# M002X.net
KiCad netlist of a schematic drawn in EAGLE
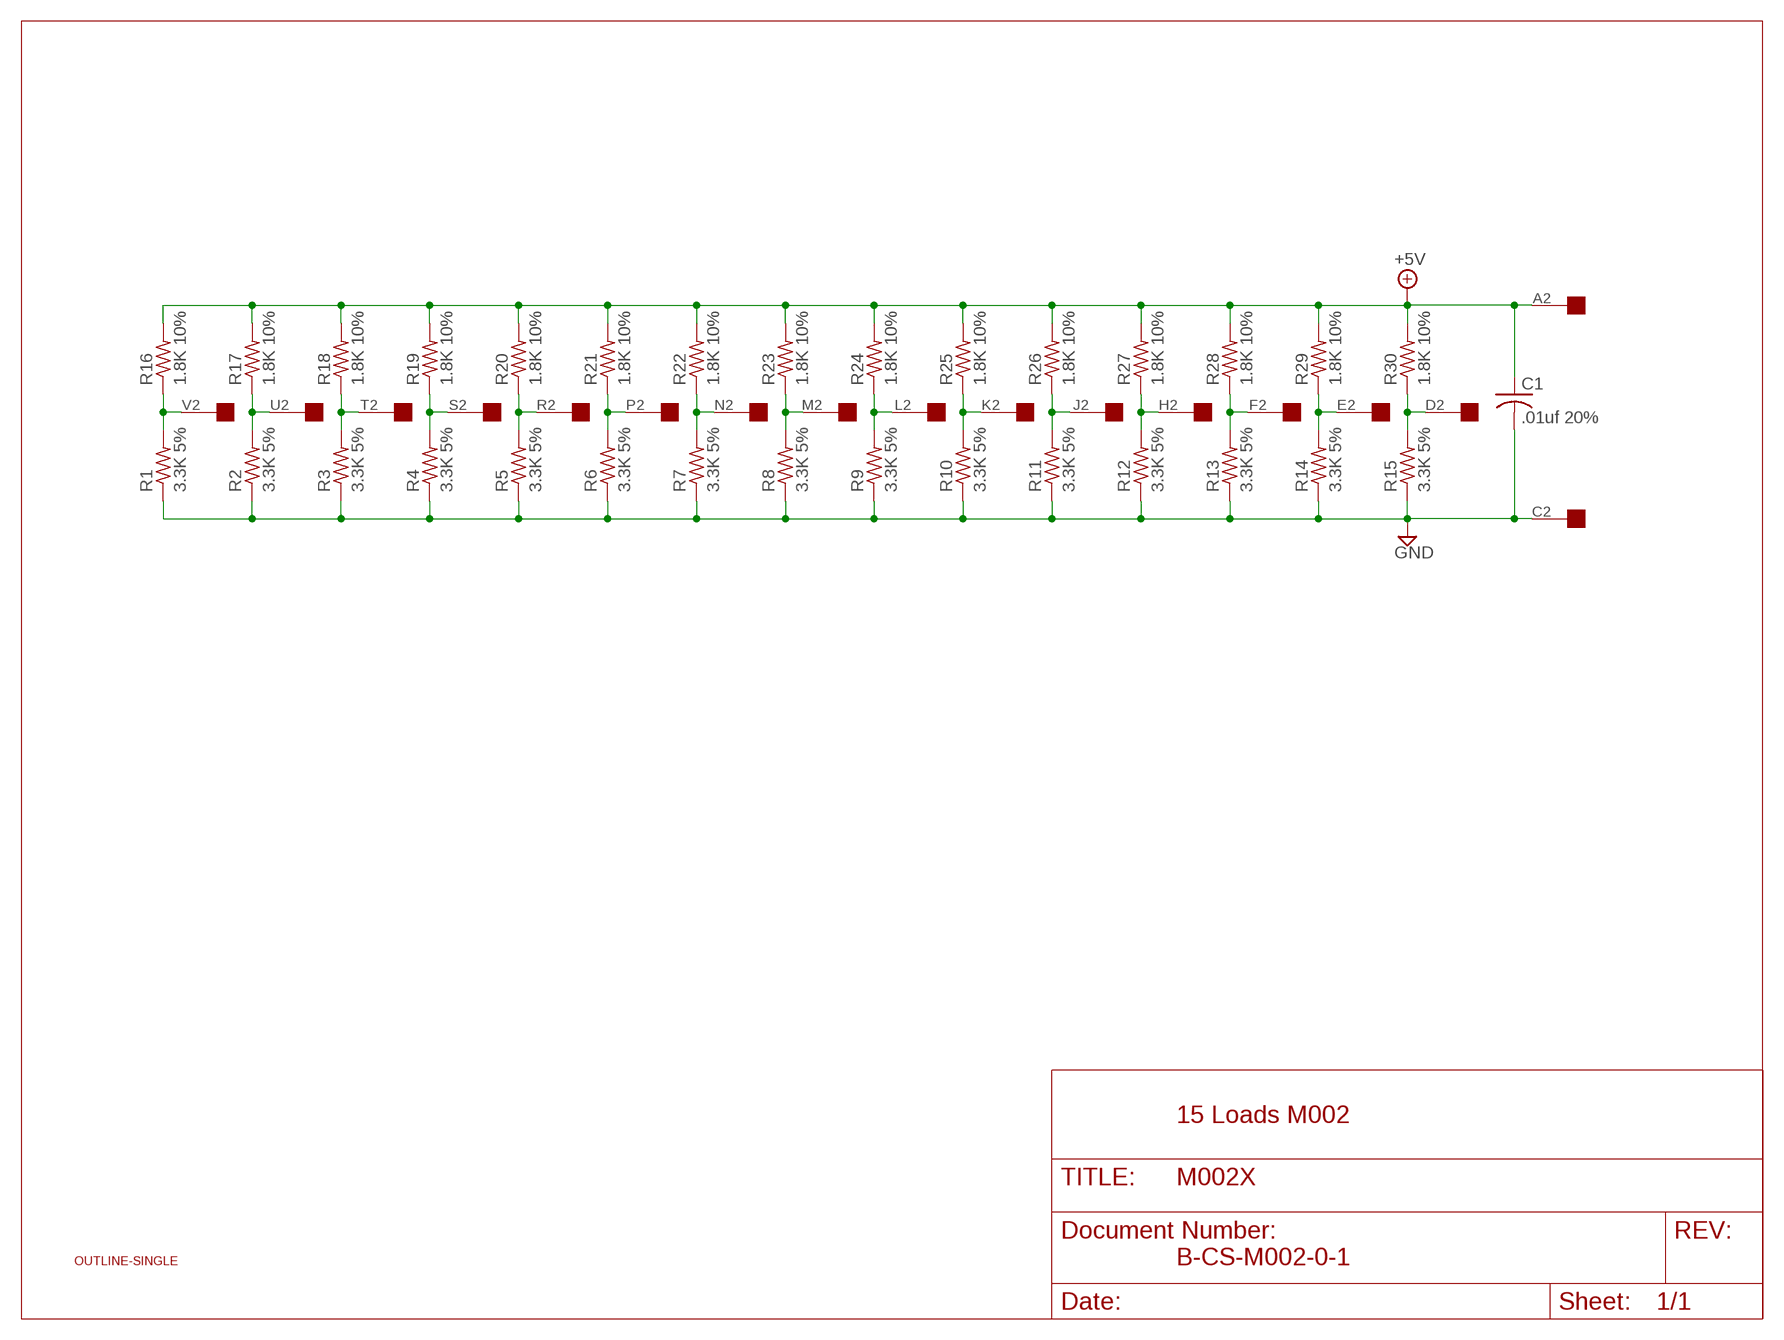
[diagram p0: schematic, sheet 1]

(export (version "E")
  (design (tool "Eeschema 10.0.6"))
  (components
    (comp (ref "C1")
      (value ".01uf 20%")
      (footprint "eagle-import:C050-025X075")
      (libsource (lib "eagle-import") (part "C-US050-025X075"))
    )
    (comp (ref "R1")
      (value "3.3K 5%")
      (footprint "eagle-import:0207_10")
      (libsource (lib "eagle-import") (part "R-US_0207/10"))
    )
    (comp (ref "R2")
      (value "3.3K 5%")
      (footprint "eagle-import:0207_10")
      (libsource (lib "eagle-import") (part "R-US_0207/10"))
    )
    (comp (ref "R3")
      (value "3.3K 5%")
      (footprint "eagle-import:0207_10")
      (libsource (lib "eagle-import") (part "R-US_0207/10"))
    )
    (comp (ref "R4")
      (value "3.3K 5%")
      (footprint "eagle-import:0207_10")
      (libsource (lib "eagle-import") (part "R-US_0207/10"))
    )
    (comp (ref "R5")
      (value "3.3K 5%")
      (footprint "eagle-import:0207_10")
      (libsource (lib "eagle-import") (part "R-US_0207/10"))
    )
    (comp (ref "R6")
      (value "3.3K 5%")
      (footprint "eagle-import:0207_10")
      (libsource (lib "eagle-import") (part "R-US_0207/10"))
    )
    (comp (ref "R7")
      (value "3.3K 5%")
      (footprint "eagle-import:0207_10")
      (libsource (lib "eagle-import") (part "R-US_0207/10"))
    )
    (comp (ref "R8")
      (value "3.3K 5%")
      (footprint "eagle-import:0207_10")
      (libsource (lib "eagle-import") (part "R-US_0207/10"))
    )
    (comp (ref "R9")
      (value "3.3K 5%")
      (footprint "eagle-import:0207_10")
      (libsource (lib "eagle-import") (part "R-US_0207/10"))
    )
    (comp (ref "R10")
      (value "3.3K 5%")
      (footprint "eagle-import:0207_10")
      (libsource (lib "eagle-import") (part "R-US_0207/10"))
    )
    (comp (ref "R11")
      (value "3.3K 5%")
      (footprint "eagle-import:0207_10")
      (libsource (lib "eagle-import") (part "R-US_0207/10"))
    )
    (comp (ref "R12")
      (value "3.3K 5%")
      (footprint "eagle-import:0207_10")
      (libsource (lib "eagle-import") (part "R-US_0207/10"))
    )
    (comp (ref "R13")
      (value "3.3K 5%")
      (footprint "eagle-import:0207_10")
      (libsource (lib "eagle-import") (part "R-US_0207/10"))
    )
    (comp (ref "R14")
      (value "3.3K 5%")
      (footprint "eagle-import:0207_10")
      (libsource (lib "eagle-import") (part "R-US_0207/10"))
    )
    (comp (ref "R15")
      (value "3.3K 5%")
      (footprint "eagle-import:0207_10")
      (libsource (lib "eagle-import") (part "R-US_0207/10"))
    )
    (comp (ref "R16")
      (value "1.8K 10%")
      (footprint "eagle-import:0207_10")
      (libsource (lib "eagle-import") (part "R-US_0207/10"))
    )
    (comp (ref "R17")
      (value "1.8K 10%")
      (footprint "eagle-import:0207_10")
      (libsource (lib "eagle-import") (part "R-US_0207/10"))
    )
    (comp (ref "R18")
      (value "1.8K 10%")
      (footprint "eagle-import:0207_10")
      (libsource (lib "eagle-import") (part "R-US_0207/10"))
    )
    (comp (ref "R19")
      (value "1.8K 10%")
      (footprint "eagle-import:0207_10")
      (libsource (lib "eagle-import") (part "R-US_0207/10"))
    )
    (comp (ref "R20")
      (value "1.8K 10%")
      (footprint "eagle-import:0207_10")
      (libsource (lib "eagle-import") (part "R-US_0207/10"))
    )
    (comp (ref "R21")
      (value "1.8K 10%")
      (footprint "eagle-import:0207_10")
      (libsource (lib "eagle-import") (part "R-US_0207/10"))
    )
    (comp (ref "R22")
      (value "1.8K 10%")
      (footprint "eagle-import:0207_10")
      (libsource (lib "eagle-import") (part "R-US_0207/10"))
    )
    (comp (ref "R23")
      (value "1.8K 10%")
      (footprint "eagle-import:0207_10")
      (libsource (lib "eagle-import") (part "R-US_0207/10"))
    )
    (comp (ref "R24")
      (value "1.8K 10%")
      (footprint "eagle-import:0207_10")
      (libsource (lib "eagle-import") (part "R-US_0207/10"))
    )
    (comp (ref "R25")
      (value "1.8K 10%")
      (footprint "eagle-import:0207_10")
      (libsource (lib "eagle-import") (part "R-US_0207/10"))
    )
    (comp (ref "R26")
      (value "1.8K 10%")
      (footprint "eagle-import:0207_10")
      (libsource (lib "eagle-import") (part "R-US_0207/10"))
    )
    (comp (ref "R27")
      (value "1.8K 10%")
      (footprint "eagle-import:0207_10")
      (libsource (lib "eagle-import") (part "R-US_0207/10"))
    )
    (comp (ref "R28")
      (value "1.8K 10%")
      (footprint "eagle-import:0207_10")
      (libsource (lib "eagle-import") (part "R-US_0207/10"))
    )
    (comp (ref "R29")
      (value "1.8K 10%")
      (footprint "eagle-import:0207_10")
      (libsource (lib "eagle-import") (part "R-US_0207/10"))
    )
    (comp (ref "R30")
      (value "1.8K 10%")
      (footprint "eagle-import:0207_10")
      (libsource (lib "eagle-import") (part "R-US_0207/10"))
    )
    (comp (ref "U$1")
      (value "OUTLINE-SINGLE")
      (footprint "eagle-import:SINGLE")
      (libsource (lib "eagle-import") (part "OUTLINE-SINGLE"))
    )
    (comp (ref "U$2")
      (value "EDGE-1")
      (footprint "eagle-import:EDGE-CON1")
      (libsource (lib "eagle-import") (part "EDGE-1"))
    )
  )
  (nets
    (net (code "1") (name "+5V") (class "Default")
      (node (ref "C1") (pin "1") (pinfunction "1_1") (pintype "passive"))
      (node (ref "R16") (pin "2") (pinfunction "2_2") (pintype "passive"))
      (node (ref "R17") (pin "2") (pinfunction "2_2") (pintype "passive"))
      (node (ref "R18") (pin "2") (pinfunction "2_2") (pintype "passive"))
      (node (ref "R19") (pin "2") (pinfunction "2_2") (pintype "passive"))
      (node (ref "R20") (pin "2") (pinfunction "2_2") (pintype "passive"))
      (node (ref "R21") (pin "2") (pinfunction "2_2") (pintype "passive"))
      (node (ref "R22") (pin "2") (pinfunction "2_2") (pintype "passive"))
      (node (ref "R23") (pin "2") (pinfunction "2_2") (pintype "passive"))
      (node (ref "R24") (pin "2") (pinfunction "2_2") (pintype "passive"))
      (node (ref "R25") (pin "2") (pinfunction "2_2") (pintype "passive"))
      (node (ref "R26") (pin "2") (pinfunction "2_2") (pintype "passive"))
      (node (ref "R27") (pin "2") (pinfunction "2_2") (pintype "passive"))
      (node (ref "R28") (pin "2") (pinfunction "2_2") (pintype "passive"))
      (node (ref "R29") (pin "2") (pinfunction "2_2") (pintype "passive"))
      (node (ref "R30") (pin "2") (pinfunction "2_2") (pintype "passive"))
      (node (ref "U$2") (pin "A2") (pinfunction "1_A2") (pintype "bidirectional"))
    )
    (net (code "2") (name "GND") (class "Default")
      (node (ref "C1") (pin "2") (pinfunction "2_2") (pintype "passive"))
      (node (ref "R1") (pin "1") (pinfunction "1_1") (pintype "passive"))
      (node (ref "R10") (pin "1") (pinfunction "1_1") (pintype "passive"))
      (node (ref "R11") (pin "1") (pinfunction "1_1") (pintype "passive"))
      (node (ref "R12") (pin "1") (pinfunction "1_1") (pintype "passive"))
      (node (ref "R13") (pin "1") (pinfunction "1_1") (pintype "passive"))
      (node (ref "R14") (pin "1") (pinfunction "1_1") (pintype "passive"))
      (node (ref "R15") (pin "1") (pinfunction "1_1") (pintype "passive"))
      (node (ref "R2") (pin "1") (pinfunction "1_1") (pintype "passive"))
      (node (ref "R3") (pin "1") (pinfunction "1_1") (pintype "passive"))
      (node (ref "R4") (pin "1") (pinfunction "1_1") (pintype "passive"))
      (node (ref "R5") (pin "1") (pinfunction "1_1") (pintype "passive"))
      (node (ref "R6") (pin "1") (pinfunction "1_1") (pintype "passive"))
      (node (ref "R7") (pin "1") (pinfunction "1_1") (pintype "passive"))
      (node (ref "R8") (pin "1") (pinfunction "1_1") (pintype "passive"))
      (node (ref "R9") (pin "1") (pinfunction "1_1") (pintype "passive"))
      (node (ref "U$2") (pin "C2") (pinfunction "1_C2") (pintype "bidirectional"))
    )
    (net (code "3") (name "Net-(U$2D-1)") (class "Default")
      (node (ref "R15") (pin "2") (pinfunction "2_2") (pintype "passive"))
      (node (ref "R30") (pin "1") (pinfunction "1_1") (pintype "passive"))
      (node (ref "U$2") (pin "D2") (pinfunction "1_D2") (pintype "bidirectional"))
    )
    (net (code "4") (name "Net-(U$2E-1)") (class "Default")
      (node (ref "R14") (pin "2") (pinfunction "2_2") (pintype "passive"))
      (node (ref "R29") (pin "1") (pinfunction "1_1") (pintype "passive"))
      (node (ref "U$2") (pin "E2") (pinfunction "1_E2") (pintype "bidirectional"))
    )
    (net (code "5") (name "Net-(U$2F-1)") (class "Default")
      (node (ref "R13") (pin "2") (pinfunction "2_2") (pintype "passive"))
      (node (ref "R28") (pin "1") (pinfunction "1_1") (pintype "passive"))
      (node (ref "U$2") (pin "F2") (pinfunction "1_F2") (pintype "bidirectional"))
    )
    (net (code "6") (name "Net-(U$2G-1)") (class "Default")
      (node (ref "R12") (pin "2") (pinfunction "2_2") (pintype "passive"))
      (node (ref "R27") (pin "1") (pinfunction "1_1") (pintype "passive"))
      (node (ref "U$2") (pin "H2") (pinfunction "1_H2") (pintype "bidirectional"))
    )
    (net (code "7") (name "Net-(U$2H-1)") (class "Default")
      (node (ref "R11") (pin "2") (pinfunction "2_2") (pintype "passive"))
      (node (ref "R26") (pin "1") (pinfunction "1_1") (pintype "passive"))
      (node (ref "U$2") (pin "J2") (pinfunction "1_J2") (pintype "bidirectional"))
    )
    (net (code "8") (name "Net-(U$2I-1)") (class "Default")
      (node (ref "R10") (pin "2") (pinfunction "2_2") (pintype "passive"))
      (node (ref "R25") (pin "1") (pinfunction "1_1") (pintype "passive"))
      (node (ref "U$2") (pin "K2") (pinfunction "1_K2") (pintype "bidirectional"))
    )
    (net (code "9") (name "Net-(U$2J-1)") (class "Default")
      (node (ref "R24") (pin "1") (pinfunction "1_1") (pintype "passive"))
      (node (ref "R9") (pin "2") (pinfunction "2_2") (pintype "passive"))
      (node (ref "U$2") (pin "L2") (pinfunction "1_L2") (pintype "bidirectional"))
    )
    (net (code "10") (name "Net-(U$2K-1)") (class "Default")
      (node (ref "R23") (pin "1") (pinfunction "1_1") (pintype "passive"))
      (node (ref "R8") (pin "2") (pinfunction "2_2") (pintype "passive"))
      (node (ref "U$2") (pin "M2") (pinfunction "1_M2") (pintype "bidirectional"))
    )
    (net (code "11") (name "Net-(U$2L-1)") (class "Default")
      (node (ref "R22") (pin "1") (pinfunction "1_1") (pintype "passive"))
      (node (ref "R7") (pin "2") (pinfunction "2_2") (pintype "passive"))
      (node (ref "U$2") (pin "N2") (pinfunction "1_N2") (pintype "bidirectional"))
    )
    (net (code "12") (name "Net-(U$2M-1)") (class "Default")
      (node (ref "R21") (pin "1") (pinfunction "1_1") (pintype "passive"))
      (node (ref "R6") (pin "2") (pinfunction "2_2") (pintype "passive"))
      (node (ref "U$2") (pin "P2") (pinfunction "1_P2") (pintype "bidirectional"))
    )
    (net (code "13") (name "Net-(U$2N-1)") (class "Default")
      (node (ref "R20") (pin "1") (pinfunction "1_1") (pintype "passive"))
      (node (ref "R5") (pin "2") (pinfunction "2_2") (pintype "passive"))
      (node (ref "U$2") (pin "R2") (pinfunction "1_R2") (pintype "bidirectional"))
    )
    (net (code "14") (name "Net-(U$2O-1)") (class "Default")
      (node (ref "R19") (pin "1") (pinfunction "1_1") (pintype "passive"))
      (node (ref "R4") (pin "2") (pinfunction "2_2") (pintype "passive"))
      (node (ref "U$2") (pin "S2") (pinfunction "1_S2") (pintype "bidirectional"))
    )
    (net (code "15") (name "Net-(U$2P-1)") (class "Default")
      (node (ref "R18") (pin "1") (pinfunction "1_1") (pintype "passive"))
      (node (ref "R3") (pin "2") (pinfunction "2_2") (pintype "passive"))
      (node (ref "U$2") (pin "T2") (pinfunction "1_T2") (pintype "bidirectional"))
    )
    (net (code "16") (name "Net-(U$2Q-1)") (class "Default")
      (node (ref "R17") (pin "1") (pinfunction "1_1") (pintype "passive"))
      (node (ref "R2") (pin "2") (pinfunction "2_2") (pintype "passive"))
      (node (ref "U$2") (pin "U2") (pinfunction "1_U2") (pintype "bidirectional"))
    )
    (net (code "17") (name "Net-(U$2R-1)") (class "Default")
      (node (ref "R1") (pin "2") (pinfunction "2_2") (pintype "passive"))
      (node (ref "R16") (pin "1") (pinfunction "1_1") (pintype "passive"))
      (node (ref "U$2") (pin "V2") (pinfunction "1_V2") (pintype "bidirectional"))
    )
  )
)
